# untitled.net
KiCad netlist of a schematic drawn in EAGLE
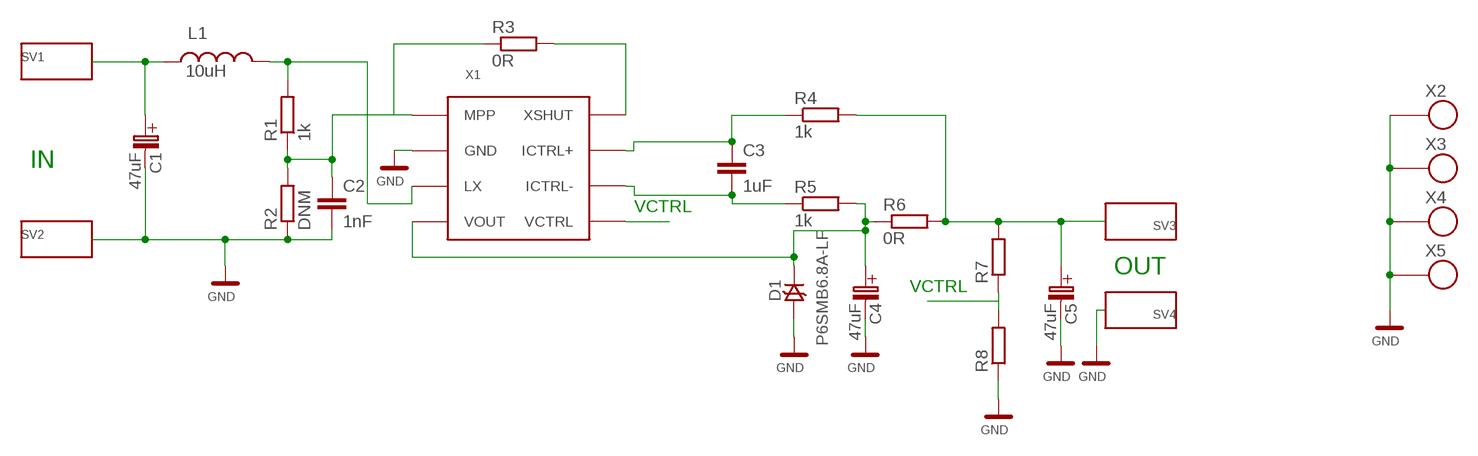
[diagram p0: schematic, sheet 1]

(export (version "E")
  (design (tool "Eeschema 10.0.6"))
  (components
    (comp (ref "C1") (value "47uF") (footprint "eagle-import:C") (libsource (lib "eagle-import") (part "C")))
    (comp (ref "C2")
      (value "1nF")
      (footprint "eagle-import:C0805")
      (libsource (lib "eagle-import") (part "C0805"))
    )
    (comp (ref "C3")
      (value "1uF")
      (footprint "eagle-import:C0805")
      (libsource (lib "eagle-import") (part "C0805"))
    )
    (comp (ref "C4") (value "47uF") (footprint "eagle-import:C") (libsource (lib "eagle-import") (part "C")))
    (comp (ref "C5") (value "47uF") (footprint "eagle-import:C") (libsource (lib "eagle-import") (part "C")))
    (comp (ref "D1")
      (value "P6SMB6.8A-LF")
      (footprint "eagle-import:SMB")
      (libsource (lib "eagle-import") (part "D-TRANSIL"))
    )
    (comp (ref "L1")
      (value "10uH")
      (footprint "eagle-import:DE1205-10")
      (libsource (lib "eagle-import") (part "DE1205-10"))
    )
    (comp (ref "R1")
      (value "1k")
      (footprint "eagle-import:0805")
      (libsource (lib "eagle-import") (part "R0805"))
    )
    (comp (ref "R2")
      (value "DNM")
      (footprint "eagle-import:0805")
      (libsource (lib "eagle-import") (part "R0805"))
    )
    (comp (ref "R3")
      (value "0R")
      (footprint "eagle-import:1206")
      (libsource (lib "eagle-import") (part "R1206"))
    )
    (comp (ref "R4")
      (value "1k")
      (footprint "eagle-import:0805")
      (libsource (lib "eagle-import") (part "R0805"))
    )
    (comp (ref "R5")
      (value "1k")
      (footprint "eagle-import:0805")
      (libsource (lib "eagle-import") (part "R0805"))
    )
    (comp (ref "R6")
      (value "0R")
      (footprint "eagle-import:1206")
      (libsource (lib "eagle-import") (part "R1206"))
    )
    (comp (ref "R7")
      (value "R0805")
      (footprint "eagle-import:0805")
      (libsource (lib "eagle-import") (part "R0805"))
    )
    (comp (ref "R8")
      (value "R0805")
      (footprint "eagle-import:0805")
      (libsource (lib "eagle-import") (part "R0805"))
    )
    (comp (ref "SV1")
      (value "WAGO256")
      (footprint "eagle-import:WAGO256")
      (libsource (lib "eagle-import") (part "WAGO256"))
    )
    (comp (ref "SV2")
      (value "WAGO256")
      (footprint "eagle-import:WAGO256")
      (libsource (lib "eagle-import") (part "WAGO256"))
    )
    (comp (ref "SV3")
      (value "WAGO256")
      (footprint "eagle-import:WAGO256")
      (libsource (lib "eagle-import") (part "WAGO256"))
    )
    (comp (ref "SV4")
      (value "WAGO256")
      (footprint "eagle-import:WAGO256")
      (libsource (lib "eagle-import") (part "WAGO256"))
    )
    (comp (ref "X1")
      (value "SPV1040")
      (footprint "eagle-import:TSSOP8")
      (libsource (lib "eagle-import") (part "SPV1040"))
    )
    (comp (ref "X2")
      (value "SROUB3M")
      (footprint "eagle-import:SROUB3M")
      (libsource (lib "eagle-import") (part "SROUB3M"))
    )
    (comp (ref "X3")
      (value "SROUB3M")
      (footprint "eagle-import:SROUB3M")
      (libsource (lib "eagle-import") (part "SROUB3M"))
    )
    (comp (ref "X4")
      (value "SROUB3M")
      (footprint "eagle-import:SROUB3M")
      (libsource (lib "eagle-import") (part "SROUB3M"))
    )
    (comp (ref "X5")
      (value "SROUB3M")
      (footprint "eagle-import:SROUB3M")
      (libsource (lib "eagle-import") (part "SROUB3M"))
    )
  )
  (nets
    (net (code "1") (name "/VCTRL") (class "Default")
      (node (ref "R7") (pin "1") (pinfunction "1_1") (pintype "passive"))
      (node (ref "R8") (pin "2") (pinfunction "2_2") (pintype "passive"))
      (node (ref "X1") (pin "5") (pinfunction "VCTRL_5") (pintype "bidirectional"))
    )
    (net (code "2") (name "GND") (class "Default")
      (node (ref "C1") (pin "-") (pinfunction "C_EL-_-") (pintype "passive"))
      (node (ref "C2") (pin "2") (pinfunction "2_2") (pintype "passive"))
      (node (ref "C4") (pin "-") (pinfunction "C_EL-_-") (pintype "passive"))
      (node (ref "C5") (pin "-") (pinfunction "C_EL-_-") (pintype "passive"))
      (node (ref "D1") (pin "A") (pinfunction "A_A") (pintype "passive"))
      (node (ref "R2") (pin "1") (pinfunction "1_1") (pintype "passive"))
      (node (ref "R8") (pin "1") (pinfunction "1_1") (pintype "passive"))
      (node (ref "SV2") (pin "1") (pinfunction "P$1_1") (pintype "passive"))
      (node (ref "SV2") (pin "A1") (pinfunction "P$1_A1") (pintype "passive"))
      (node (ref "SV4") (pin "1") (pinfunction "P$1_1") (pintype "passive"))
      (node (ref "SV4") (pin "A1") (pinfunction "P$1_A1") (pintype "passive"))
      (node (ref "X1") (pin "2") (pinfunction "GND_2") (pintype "bidirectional"))
      (node (ref "X2") (pin "P$1") (pinfunction "P$1_P$1") (pintype "bidirectional"))
      (node (ref "X3") (pin "P$1") (pinfunction "P$1_P$1") (pintype "bidirectional"))
      (node (ref "X4") (pin "P$1") (pinfunction "P$1_P$1") (pintype "bidirectional"))
      (node (ref "X5") (pin "P$1") (pinfunction "P$1_P$1") (pintype "bidirectional"))
    )
    (net (code "3") (name "Net-(C1-C_EL+)") (class "Default")
      (node (ref "C1") (pin "+") (pinfunction "C_EL+_+") (pintype "passive"))
      (node (ref "L1") (pin "P$1") (pinfunction "1_P$1") (pintype "passive"))
      (node (ref "SV1") (pin "1") (pinfunction "P$1_1") (pintype "passive"))
      (node (ref "SV1") (pin "A1") (pinfunction "P$1_A1") (pintype "passive"))
    )
    (net (code "4") (name "Net-(C4-C_EL+)") (class "Default")
      (node (ref "C4") (pin "+") (pinfunction "C_EL+_+") (pintype "passive"))
      (node (ref "D1") (pin "K") (pinfunction "K_K") (pintype "passive"))
      (node (ref "R5") (pin "2") (pinfunction "2_2") (pintype "passive"))
      (node (ref "R6") (pin "1") (pinfunction "1_1") (pintype "passive"))
      (node (ref "X1") (pin "4") (pinfunction "VOUT_4") (pintype "bidirectional"))
    )
    (net (code "5") (name "Net-(C5-C_EL+)") (class "Default")
      (node (ref "C5") (pin "+") (pinfunction "C_EL+_+") (pintype "passive"))
      (node (ref "R4") (pin "2") (pinfunction "2_2") (pintype "passive"))
      (node (ref "R6") (pin "2") (pinfunction "2_2") (pintype "passive"))
      (node (ref "R7") (pin "2") (pinfunction "2_2") (pintype "passive"))
      (node (ref "SV3") (pin "1") (pinfunction "P$1_1") (pintype "passive"))
      (node (ref "SV3") (pin "A1") (pinfunction "P$1_A1") (pintype "passive"))
    )
    (net (code "6") (name "Net-(L1-2)") (class "Default")
      (node (ref "L1") (pin "P$2") (pinfunction "2_P$2") (pintype "passive"))
      (node (ref "R1") (pin "2") (pinfunction "2_2") (pintype "passive"))
      (node (ref "X1") (pin "3") (pinfunction "LX_3") (pintype "bidirectional"))
    )
    (net (code "7") (name "Net-(X1-ICTRL+)") (class "Default")
      (node (ref "C3") (pin "1") (pinfunction "1_1") (pintype "passive"))
      (node (ref "R4") (pin "1") (pinfunction "1_1") (pintype "passive"))
      (node (ref "X1") (pin "7") (pinfunction "ICTRL+_7") (pintype "bidirectional"))
    )
    (net (code "8") (name "Net-(X1-ICTRL-)") (class "Default")
      (node (ref "C3") (pin "2") (pinfunction "2_2") (pintype "passive"))
      (node (ref "R5") (pin "1") (pinfunction "1_1") (pintype "passive"))
      (node (ref "X1") (pin "6") (pinfunction "ICTRL-_6") (pintype "bidirectional"))
    )
    (net (code "9") (name "Net-(X1-MPP)") (class "Default")
      (node (ref "C2") (pin "1") (pinfunction "1_1") (pintype "passive"))
      (node (ref "R1") (pin "1") (pinfunction "1_1") (pintype "passive"))
      (node (ref "R2") (pin "2") (pinfunction "2_2") (pintype "passive"))
      (node (ref "R3") (pin "1") (pinfunction "1_1") (pintype "passive"))
      (node (ref "X1") (pin "1") (pinfunction "MPP_1") (pintype "bidirectional"))
    )
    (net (code "10") (name "Net-(X1-XSHUT)") (class "Default")
      (node (ref "R3") (pin "2") (pinfunction "2_2") (pintype "passive"))
      (node (ref "X1") (pin "8") (pinfunction "XSHUT_8") (pintype "bidirectional"))
    )
  )
)
